# Power_Supply_no_IC.net
KiCad netlist of a schematic drawn in Altium Designer
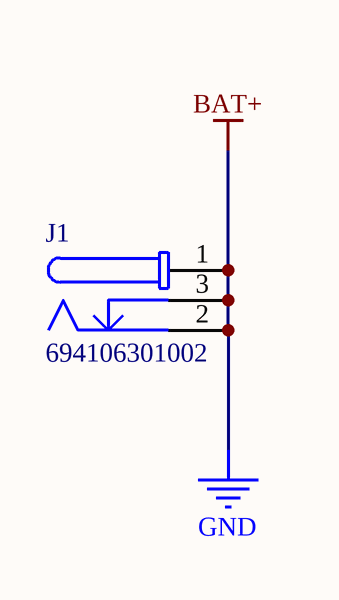
[diagram p0: Power_Supply_no_IC.SchDoc]

(export (version "E")
  (design (tool "Eeschema 10.0.6"))
  (components
    (comp (ref "J1")
      (value "694106301002")
      (footprint "694106301002")
      (fields (field (name "MANUFACTURER") "Wurth Electronics"))
      (libsource (lib "Altium Content Vault") (part "DC Power Jack"))
    )
  )
  (nets
    (net (code "1") (name "BAT+") (class "Default")
      (node (ref "J1") (pin "1") (pinfunction "1_1") (pintype "passive"))
      (node (ref "J1") (pin "2") (pinfunction "2_2") (pintype "passive"))
      (node (ref "J1") (pin "3") (pinfunction "3_3") (pintype "passive"))
    )
  )
)
